# ardunio-physics-board-v4.net
KiCad netlist of a schematic drawn in EAGLE
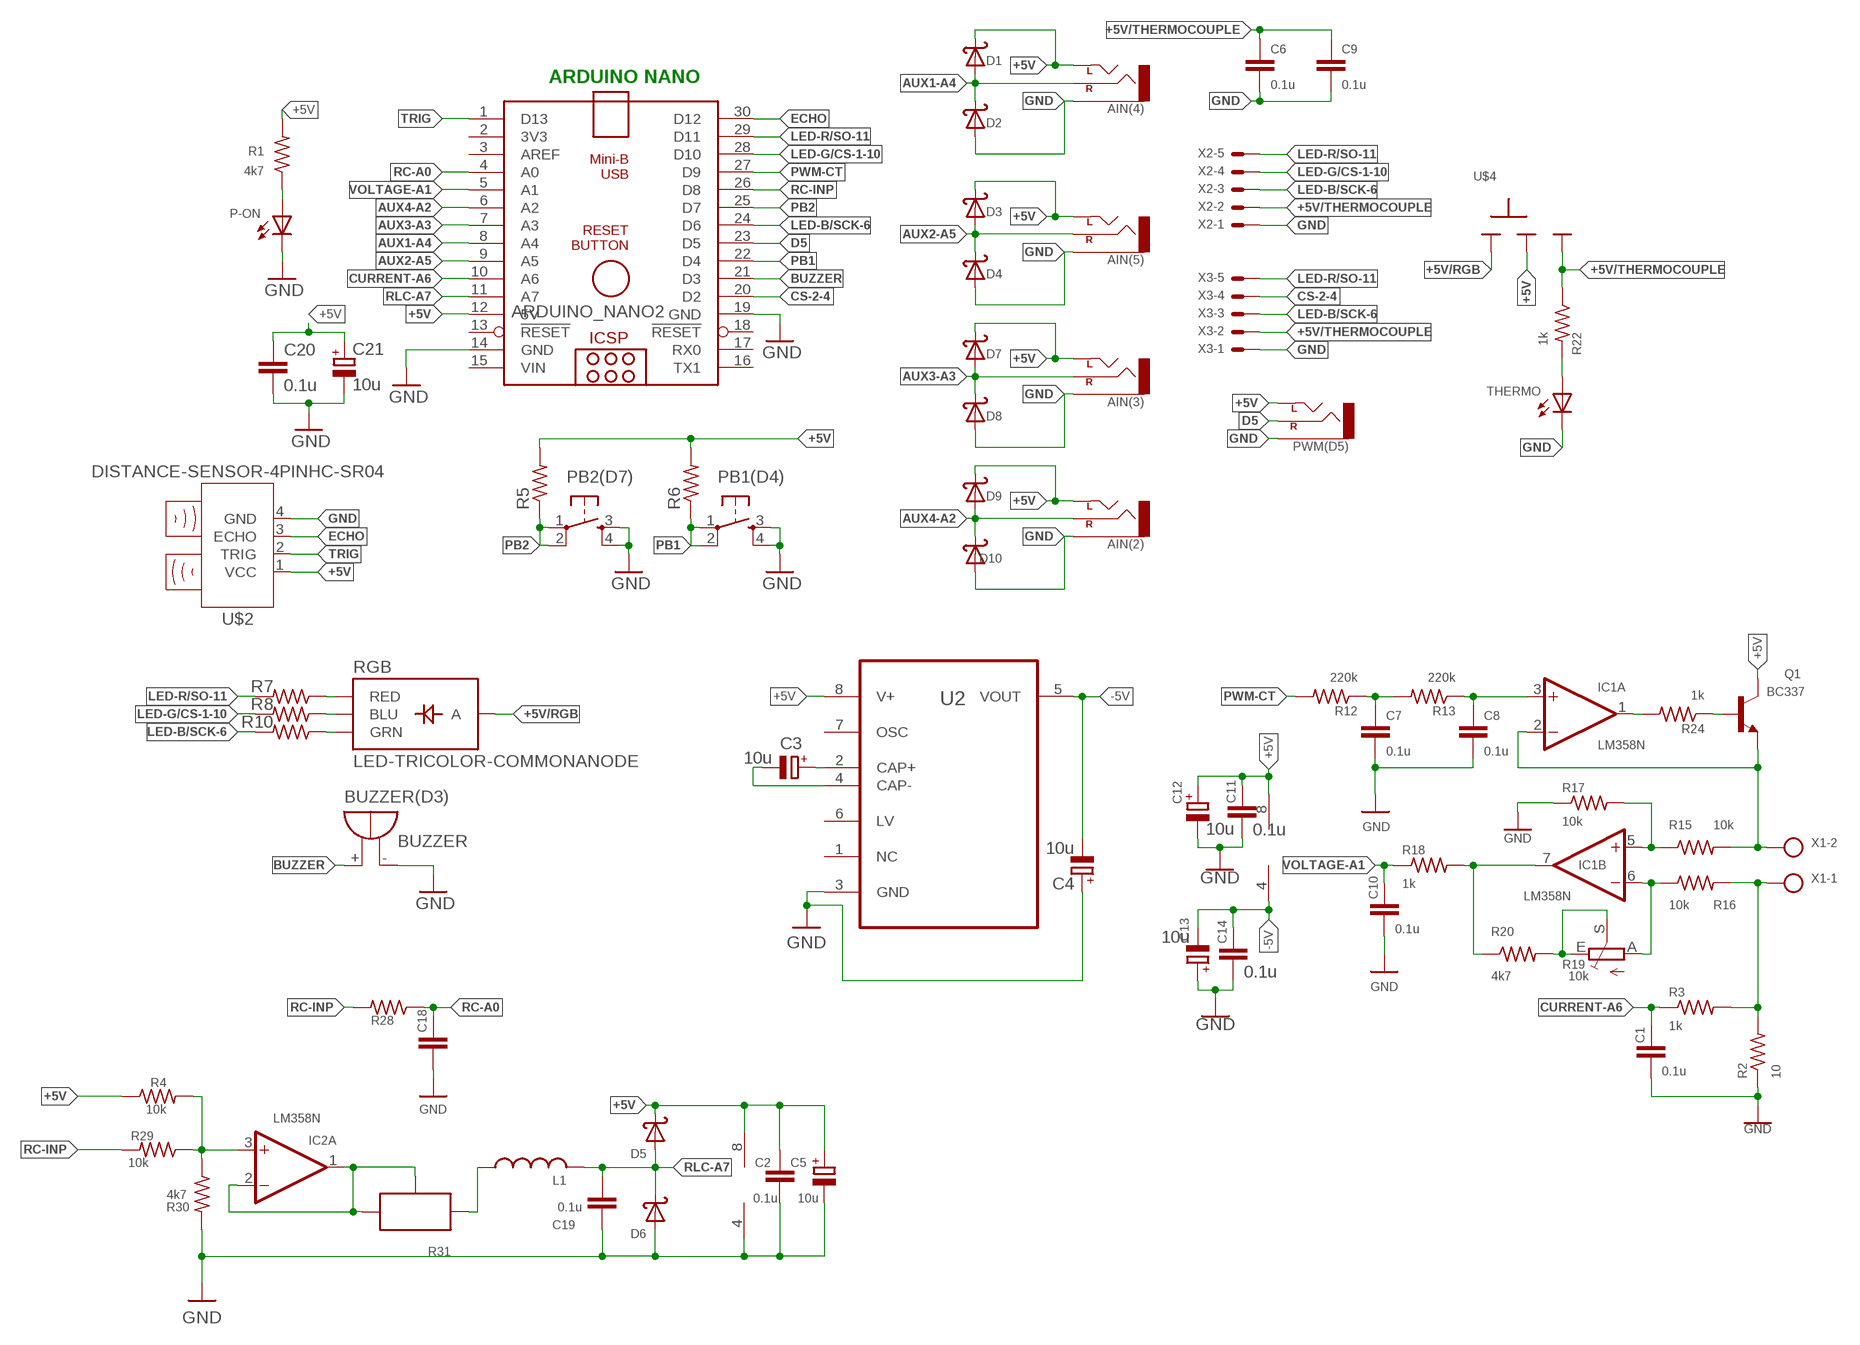
[diagram p0: schematic, sheet 1]

(export (version "E")
  (design (tool "Eeschema 10.0.6"))
  (components
    (comp (ref "AIN(2)")
      (value "AUX-CONNECTOR_CEDT_JANUARY_2015_V5_AUDIO-JACKPTH")
      (footprint "eagle-import:AUX-CONNECTOR_CEDT_JANUARY_2015_V5_AUDIO-JACK")
      (libsource (lib "eagle-import") (part "AUX-CONNECTOR_CEDT_JANUARY_2015_V5_AUDIO-JACKPTH"))
    )
    (comp (ref "AIN(3)")
      (value "AUX-CONNECTOR_CEDT_JANUARY_2015_V5_AUDIO-JACKPTH")
      (footprint "eagle-import:AUX-CONNECTOR_CEDT_JANUARY_2015_V5_AUDIO-JACK")
      (libsource (lib "eagle-import") (part "AUX-CONNECTOR_CEDT_JANUARY_2015_V5_AUDIO-JACKPTH"))
    )
    (comp (ref "AIN(4)")
      (value "AUX-CONNECTOR_CEDT_JANUARY_2015_V5_AUDIO-JACKPTH")
      (footprint "eagle-import:AUX-CONNECTOR_CEDT_JANUARY_2015_V5_AUDIO-JACK")
      (libsource (lib "eagle-import") (part "AUX-CONNECTOR_CEDT_JANUARY_2015_V5_AUDIO-JACKPTH"))
    )
    (comp (ref "AIN(5)")
      (value "AUX-CONNECTOR_CEDT_JANUARY_2015_V5_AUDIO-JACKPTH")
      (footprint "eagle-import:AUX-CONNECTOR_CEDT_JANUARY_2015_V5_AUDIO-JACK")
      (libsource (lib "eagle-import") (part "AUX-CONNECTOR_CEDT_JANUARY_2015_V5_AUDIO-JACKPTH"))
    )
    (comp (ref "ARDUINO_NANO2")
      (value "ARDUINONANOV30_ARDUINO_NANO")
      (footprint "eagle-import:ARDUINONANOV30_ARDUINO_NANO")
      (libsource (lib "eagle-import") (part "ARDUINONANOV30_ARDUINO_NANO"))
    )
    (comp (ref "BUZZER(D3)")
      (value "BUZZER")
      (footprint "eagle-import:F_TMB")
      (libsource (lib "eagle-import") (part "BUZZER"))
    )
    (comp (ref "C1")
      (value "0.1u")
      (footprint "eagle-import:C025-025X050")
      (libsource (lib "eagle-import") (part "C-EU025-025X050"))
    )
    (comp (ref "C2")
      (value "0.1u")
      (footprint "eagle-import:C025-025X050")
      (libsource (lib "eagle-import") (part "C-EU025-025X050"))
    )
    (comp (ref "C3")
      (value "10u")
      (footprint "eagle-import:TT2D5")
      (libsource (lib "eagle-import") (part "CPOL-EUTT2D5"))
    )
    (comp (ref "C4")
      (value "10u")
      (footprint "eagle-import:TT2D5")
      (libsource (lib "eagle-import") (part "CPOL-EUTT2D5"))
    )
    (comp (ref "C5")
      (value "10u")
      (footprint "eagle-import:TT2D5")
      (libsource (lib "eagle-import") (part "CPOL-EUTT2D5"))
    )
    (comp (ref "C6")
      (value "0.1u")
      (footprint "eagle-import:C025-024X044")
      (libsource (lib "eagle-import") (part "C-EU025-024X044"))
    )
    (comp (ref "C7")
      (value "0.1u")
      (footprint "eagle-import:C025-025X050")
      (libsource (lib "eagle-import") (part "C-EU025-025X050"))
    )
    (comp (ref "C8")
      (value "0.1u")
      (footprint "eagle-import:C025-025X050")
      (libsource (lib "eagle-import") (part "C-EU025-025X050"))
    )
    (comp (ref "C9")
      (value "0.1u")
      (footprint "eagle-import:C025-024X044")
      (libsource (lib "eagle-import") (part "C-EU025-024X044"))
    )
    (comp (ref "C10")
      (value "0.1u")
      (footprint "eagle-import:C025-025X050")
      (libsource (lib "eagle-import") (part "C-EU025-025X050"))
    )
    (comp (ref "C11")
      (value "0.1u")
      (footprint "eagle-import:C025-025X050")
      (libsource (lib "eagle-import") (part "C-EU025-025X050"))
    )
    (comp (ref "C12")
      (value "10u")
      (footprint "eagle-import:TT2D5")
      (libsource (lib "eagle-import") (part "CPOL-EUTT2D5"))
    )
    (comp (ref "C13")
      (value "10u")
      (footprint "eagle-import:TT2D5")
      (libsource (lib "eagle-import") (part "CPOL-EUTT2D5"))
    )
    (comp (ref "C14")
      (value "0.1u")
      (footprint "eagle-import:C025-025X050")
      (libsource (lib "eagle-import") (part "C-EU025-025X050"))
    )
    (comp (ref "C18")
      (value "C-EU025-025X050")
      (footprint "eagle-import:C025-025X050")
      (libsource (lib "eagle-import") (part "C-EU025-025X050"))
    )
    (comp (ref "C19")
      (value "0.1u")
      (footprint "eagle-import:C025-025X050")
      (libsource (lib "eagle-import") (part "C-EU025-025X050"))
    )
    (comp (ref "C20")
      (value "0.1u")
      (footprint "eagle-import:C025-024X044")
      (libsource (lib "eagle-import") (part "C-EU025-024X044"))
    )
    (comp (ref "C21")
      (value "10u")
      (footprint "eagle-import:E2,5-5")
      (libsource (lib "eagle-import") (part "CPOL-EUE2.5-5"))
    )
    (comp (ref "D1")
      (value "1N5819")
      (footprint "eagle-import:DO41-10")
      (libsource (lib "eagle-import") (part "1N5819"))
    )
    (comp (ref "D2")
      (value "1N5819")
      (footprint "eagle-import:DO41-10")
      (libsource (lib "eagle-import") (part "1N5819"))
    )
    (comp (ref "D3")
      (value "1N5819")
      (footprint "eagle-import:DO41-10")
      (libsource (lib "eagle-import") (part "1N5819"))
    )
    (comp (ref "D4")
      (value "1N5819")
      (footprint "eagle-import:DO41-10")
      (libsource (lib "eagle-import") (part "1N5819"))
    )
    (comp (ref "D5")
      (value "1N5819")
      (footprint "eagle-import:DO41-10")
      (libsource (lib "eagle-import") (part "1N5819"))
    )
    (comp (ref "D6")
      (value "1N5819")
      (footprint "eagle-import:DO41-10")
      (libsource (lib "eagle-import") (part "1N5819"))
    )
    (comp (ref "D7")
      (value "1N5819")
      (footprint "eagle-import:DO41-10")
      (libsource (lib "eagle-import") (part "1N5819"))
    )
    (comp (ref "D8")
      (value "1N5819")
      (footprint "eagle-import:DO41-10")
      (libsource (lib "eagle-import") (part "1N5819"))
    )
    (comp (ref "D9")
      (value "1N5819")
      (footprint "eagle-import:DO41-10")
      (libsource (lib "eagle-import") (part "1N5819"))
    )
    (comp (ref "D10")
      (value "1N5819")
      (footprint "eagle-import:DO41-10")
      (libsource (lib "eagle-import") (part "1N5819"))
    )
    (comp (ref "IC1")
      (value "LM358N")
      (footprint "eagle-import:DIL08")
      (libsource (lib "eagle-import") (part "LM358N"))
    )
    (comp (ref "IC2")
      (value "LM358N")
      (footprint "eagle-import:DIL08")
      (libsource (lib "eagle-import") (part "LM358N"))
    )
    (comp (ref "L1")
      (value "L-US6000-XXX-RC")
      (footprint "eagle-import:6000-XXXX-RC")
      (libsource (lib "eagle-import") (part "L-US6000-XXX-RC"))
    )
    (comp (ref "P-ON")
      (value "LED3MM")
      (footprint "eagle-import:LED3MM")
      (libsource (lib "eagle-import") (part "LED3MM"))
    )
    (comp (ref "PB1(D4)")
      (value "OMRON_SWITCH_40-XX")
      (footprint "eagle-import:B3F-40XX")
      (libsource (lib "eagle-import") (part "OMRON_SWITCH_40-XX"))
    )
    (comp (ref "PB2(D7)")
      (value "OMRON_SWITCH_40-XX")
      (footprint "eagle-import:B3F-40XX")
      (libsource (lib "eagle-import") (part "OMRON_SWITCH_40-XX"))
    )
    (comp (ref "PWM(D5)")
      (value "AUX-CONNECTOR_CEDT_JANUARY_2015_V5_AUDIO-JACKPTH")
      (footprint "eagle-import:AUX-CONNECTOR_CEDT_JANUARY_2015_V5_AUDIO-JACK")
      (libsource (lib "eagle-import") (part "AUX-CONNECTOR_CEDT_JANUARY_2015_V5_AUDIO-JACKPTH"))
    )
    (comp (ref "Q1")
      (value "BC337")
      (footprint "eagle-import:TO92")
      (libsource (lib "eagle-import") (part "BC337"))
    )
    (comp (ref "R1")
      (value "4k7")
      (footprint "eagle-import:0204_7")
      (libsource (lib "eagle-import") (part "R-US_0204/7"))
    )
    (comp (ref "R2")
      (value "10")
      (footprint "eagle-import:0207_10")
      (libsource (lib "eagle-import") (part "RESISTOR0207/10"))
    )
    (comp (ref "R3")
      (value "1k")
      (footprint "eagle-import:0204_7")
      (libsource (lib "eagle-import") (part "R-US_0204/7"))
    )
    (comp (ref "R4")
      (value "10k")
      (footprint "eagle-import:0207_10")
      (libsource (lib "eagle-import") (part "R-US_0207/10"))
    )
    (comp (ref "R5")
      (value "R-US_0204/7")
      (footprint "eagle-import:0204_7")
      (libsource (lib "eagle-import") (part "R-US_0204/7"))
    )
    (comp (ref "R6")
      (value "R-US_0204/7")
      (footprint "eagle-import:0204_7")
      (libsource (lib "eagle-import") (part "R-US_0204/7"))
    )
    (comp (ref "R7")
      (value "R-US_0207/10")
      (footprint "eagle-import:0207_10")
      (libsource (lib "eagle-import") (part "R-US_0207/10"))
    )
    (comp (ref "R8")
      (value "R-US_0207/10")
      (footprint "eagle-import:0207_10")
      (libsource (lib "eagle-import") (part "R-US_0207/10"))
    )
    (comp (ref "R10")
      (value "R-US_0207/10")
      (footprint "eagle-import:0207_10")
      (libsource (lib "eagle-import") (part "R-US_0207/10"))
    )
    (comp (ref "R12")
      (value "220k")
      (footprint "eagle-import:0207_10")
      (libsource (lib "eagle-import") (part "R-US_0207/10"))
    )
    (comp (ref "R13")
      (value "220k")
      (footprint "eagle-import:0204_7")
      (libsource (lib "eagle-import") (part "R-US_0204/7"))
    )
    (comp (ref "R15")
      (value "10k")
      (footprint "eagle-import:0204_7")
      (libsource (lib "eagle-import") (part "R-US_0204/7"))
    )
    (comp (ref "R16")
      (value "10k")
      (footprint "eagle-import:0204_7")
      (libsource (lib "eagle-import") (part "R-US_0204/7"))
    )
    (comp (ref "R17")
      (value "10k")
      (footprint "eagle-import:0204_7")
      (libsource (lib "eagle-import") (part "R-US_0204/7"))
    )
    (comp (ref "R18")
      (value "1k")
      (footprint "eagle-import:0204_7")
      (libsource (lib "eagle-import") (part "R-US_0204/7"))
    )
    (comp (ref "R19")
      (value "10k")
      (footprint "eagle-import:RJ9W")
      (libsource (lib "eagle-import") (part "TRIM_EU-RJ9W"))
    )
    (comp (ref "R20")
      (value "4k7")
      (footprint "eagle-import:0204_7")
      (libsource (lib "eagle-import") (part "R-US_0204/7"))
    )
    (comp (ref "R22")
      (value "1k")
      (footprint "eagle-import:0204_7")
      (libsource (lib "eagle-import") (part "R-US_0204/7"))
    )
    (comp (ref "R24")
      (value "1k")
      (footprint "eagle-import:0204_7")
      (libsource (lib "eagle-import") (part "R-US_0204/7"))
    )
    (comp (ref "R28")
      (value "R-US_0207/10")
      (footprint "eagle-import:0207_10")
      (libsource (lib "eagle-import") (part "R-US_0207/10"))
    )
    (comp (ref "R29")
      (value "10k")
      (footprint "eagle-import:0204_7")
      (libsource (lib "eagle-import") (part "R-US_0204/7"))
    )
    (comp (ref "R30")
      (value "4k7")
      (footprint "eagle-import:0207_10")
      (libsource (lib "eagle-import") (part "R-US_0207/10"))
    )
    (comp (ref "R31")
      (value "POTNORMAL")
      (footprint "eagle-import:RJ9W")
      (libsource (lib "eagle-import") (part "POTNORMAL"))
    )
    (comp (ref "RGB")
      (value "LED-TRICOLOR-COMMONANODE")
      (footprint "eagle-import:LED-TRICOLOR-THROUGHHOLE")
      (libsource (lib "eagle-import") (part "LED-TRICOLOR-COMMONANODE"))
    )
    (comp (ref "THERMO")
      (value "LED3MM")
      (footprint "eagle-import:LED3MM")
      (libsource (lib "eagle-import") (part "LED3MM"))
    )
    (comp (ref "U$2")
      (value "DISTANCE-SENSOR-4PINHC-SR04")
      (footprint "eagle-import:HC-SR04")
      (libsource (lib "eagle-import") (part "DISTANCE-SENSOR-4PINHC-SR04"))
    )
    (comp (ref "U$4")
      (value "SLIDESWITCH-BIG")
      (footprint "eagle-import:BIGSWITCH")
      (libsource (lib "eagle-import") (part "SLIDESWITCH-BIG"))
    )
    (comp (ref "U2")
      (value "ICL7660CPAZ_ICL7660CPAZ")
      (footprint "eagle-import:ICL7660CPAZ_DIP254P762X533-8")
      (fields (field (name "MF") "Renesas Electronics") (field (name "MP") "ICL7660CPAZ"))
      (libsource (lib "eagle-import") (part "ICL7660CPAZ_ICL7660CPAZ"))
    )
    (comp (ref "X1")
      (value "AK500/2-H")
      (footprint "eagle-import:AK500_2-H")
      (libsource (lib "eagle-import") (part "AK500/2-H"))
    )
    (comp (ref "X2")
      (value "JST-XH-05-PIN-LONG-PAD")
      (footprint "eagle-import:JST-XH-05-PACKAGE-LONG-PAD")
      (libsource (lib "eagle-import") (part "JST-XH-05-PIN-LONG-PAD"))
    )
    (comp (ref "X3")
      (value "JST-XH-05-PIN-LONG-PAD")
      (footprint "eagle-import:JST-XH-05-PACKAGE-LONG-PAD")
      (libsource (lib "eagle-import") (part "JST-XH-05-PIN-LONG-PAD"))
    )
  )
  (nets
    (net (code "1") (name "+5V") (class "Default")
      (node (ref "AIN(2)") (pin "TIP") (pinfunction "LEFT_TIP") (pintype "bidirectional"))
      (node (ref "AIN(3)") (pin "TIP") (pinfunction "LEFT_TIP") (pintype "bidirectional"))
      (node (ref "AIN(4)") (pin "TIP") (pinfunction "LEFT_TIP") (pintype "bidirectional"))
      (node (ref "AIN(5)") (pin "TIP") (pinfunction "LEFT_TIP") (pintype "bidirectional"))
      (node (ref "ARDUINO_NANO2") (pin "12") (pinfunction "5V_12") (pintype "power_in"))
      (node (ref "C11") (pin "1") (pinfunction "1_1") (pintype "passive"))
      (node (ref "C12") (pin "+") (pinfunction "+_+") (pintype "passive"))
      (node (ref "C2") (pin "1") (pinfunction "1_1") (pintype "passive"))
      (node (ref "C20") (pin "1") (pinfunction "1_1") (pintype "passive"))
      (node (ref "C21") (pin "+") (pinfunction "+_+") (pintype "passive"))
      (node (ref "C5") (pin "+") (pinfunction "+_+") (pintype "passive"))
      (node (ref "D1") (pin "C") (pinfunction "C_C") (pintype "passive"))
      (node (ref "D3") (pin "C") (pinfunction "C_C") (pintype "passive"))
      (node (ref "D5") (pin "C") (pinfunction "C_C") (pintype "passive"))
      (node (ref "D7") (pin "C") (pinfunction "C_C") (pintype "passive"))
      (node (ref "D9") (pin "C") (pinfunction "C_C") (pintype "passive"))
      (node (ref "IC1") (pin "8") (pinfunction "V+_8") (pintype "power_in"))
      (node (ref "IC2") (pin "8") (pinfunction "V+_8") (pintype "power_in"))
      (node (ref "PWM(D5)") (pin "TIP") (pinfunction "LEFT_TIP") (pintype "bidirectional"))
      (node (ref "Q1") (pin "3") (pinfunction "C_3") (pintype "passive"))
      (node (ref "R1") (pin "2") (pinfunction "2_2") (pintype "passive"))
      (node (ref "R4") (pin "1") (pinfunction "1_1") (pintype "passive"))
      (node (ref "R5") (pin "2") (pinfunction "2_2") (pintype "passive"))
      (node (ref "R6") (pin "2") (pinfunction "2_2") (pintype "passive"))
      (node (ref "U$2") (pin "1") (pinfunction "VCC_1") (pintype "bidirectional"))
      (node (ref "U$4") (pin "2") (pinfunction "2_2") (pintype "bidirectional"))
      (node (ref "U2") (pin "8") (pinfunction "V+_8") (pintype "power_in"))
    )
    (net (code "2") (name "+5V{slash}RGB") (class "Default")
      (node (ref "RGB") (pin "ANODE") (pinfunction "A_ANODE") (pintype "bidirectional"))
      (node (ref "U$4") (pin "1") (pinfunction "1_1") (pintype "bidirectional"))
    )
    (net (code "3") (name "+5V{slash}THERMOCOUPLE") (class "Default")
      (node (ref "C6") (pin "1") (pinfunction "1_1") (pintype "passive"))
      (node (ref "C9") (pin "1") (pinfunction "1_1") (pintype "passive"))
      (node (ref "R22") (pin "1") (pinfunction "1_1") (pintype "passive"))
      (node (ref "U$4") (pin "3") (pinfunction "3_3") (pintype "bidirectional"))
      (node (ref "X2") (pin "2") (pinfunction "S_2") (pintype "passive"))
      (node (ref "X3") (pin "2") (pinfunction "S_2") (pintype "passive"))
    )
    (net (code "4") (name "-5V") (class "Default")
      (node (ref "C13") (pin "-") (pinfunction "-_-") (pintype "passive"))
      (node (ref "C14") (pin "1") (pinfunction "1_1") (pintype "passive"))
      (node (ref "C4") (pin "-") (pinfunction "-_-") (pintype "passive"))
      (node (ref "IC1") (pin "4") (pinfunction "V-_4") (pintype "power_in"))
      (node (ref "U2") (pin "5") (pinfunction "VOUT_5") (pintype "output"))
    )
    (net (code "5") (name "/VIN") (class "Default")
      (node (ref "ARDUINO_NANO2") (pin "15") (pinfunction "VIN_15") (pintype "power_in"))
    )
    (net (code "6") (name "AUX1-A4") (class "Default")
      (node (ref "AIN(4)") (pin "RING") (pinfunction "RIGHT_RING") (pintype "bidirectional"))
      (node (ref "ARDUINO_NANO2") (pin "8") (pinfunction "A4_8") (pintype "bidirectional"))
      (node (ref "D1") (pin "A") (pinfunction "A_A") (pintype "passive"))
      (node (ref "D2") (pin "C") (pinfunction "C_C") (pintype "passive"))
    )
    (net (code "7") (name "AUX2-A5") (class "Default")
      (node (ref "AIN(5)") (pin "RING") (pinfunction "RIGHT_RING") (pintype "bidirectional"))
      (node (ref "ARDUINO_NANO2") (pin "9") (pinfunction "A5_9") (pintype "bidirectional"))
      (node (ref "D3") (pin "A") (pinfunction "A_A") (pintype "passive"))
      (node (ref "D4") (pin "C") (pinfunction "C_C") (pintype "passive"))
    )
    (net (code "8") (name "AUX3-A3") (class "Default")
      (node (ref "AIN(3)") (pin "RING") (pinfunction "RIGHT_RING") (pintype "bidirectional"))
      (node (ref "ARDUINO_NANO2") (pin "7") (pinfunction "A3_7") (pintype "bidirectional"))
      (node (ref "D7") (pin "A") (pinfunction "A_A") (pintype "passive"))
      (node (ref "D8") (pin "C") (pinfunction "C_C") (pintype "passive"))
    )
    (net (code "9") (name "AUX4-A2") (class "Default")
      (node (ref "AIN(2)") (pin "RING") (pinfunction "RIGHT_RING") (pintype "bidirectional"))
      (node (ref "ARDUINO_NANO2") (pin "6") (pinfunction "A2_6") (pintype "bidirectional"))
      (node (ref "D10") (pin "C") (pinfunction "C_C") (pintype "passive"))
      (node (ref "D9") (pin "A") (pinfunction "A_A") (pintype "passive"))
    )
    (net (code "10") (name "BUZZER") (class "Default")
      (node (ref "ARDUINO_NANO2") (pin "21") (pinfunction "D3_21") (pintype "bidirectional"))
      (node (ref "BUZZER(D3)") (pin "+") (pinfunction "+_+") (pintype "passive"))
    )
    (net (code "11") (name "CS-2-4") (class "Default")
      (node (ref "ARDUINO_NANO2") (pin "20") (pinfunction "D2_20") (pintype "bidirectional"))
      (node (ref "X3") (pin "4") (pinfunction "S_4") (pintype "passive"))
    )
    (net (code "12") (name "CURRENT-A6") (class "Default")
      (node (ref "ARDUINO_NANO2") (pin "10") (pinfunction "A6_10") (pintype "bidirectional"))
      (node (ref "C1") (pin "1") (pinfunction "1_1") (pintype "passive"))
      (node (ref "R3") (pin "1") (pinfunction "1_1") (pintype "passive"))
    )
    (net (code "13") (name "D5") (class "Default")
      (node (ref "ARDUINO_NANO2") (pin "23") (pinfunction "D5_23") (pintype "bidirectional"))
      (node (ref "PWM(D5)") (pin "RING") (pinfunction "RIGHT_RING") (pintype "bidirectional"))
    )
    (net (code "14") (name "ECHO") (class "Default")
      (node (ref "ARDUINO_NANO2") (pin "30") (pinfunction "D12_30") (pintype "bidirectional"))
      (node (ref "U$2") (pin "3") (pinfunction "ECHO_3") (pintype "bidirectional"))
    )
    (net (code "15") (name "GND") (class "Default")
      (node (ref "AIN(2)") (pin "SLEEVE") (pinfunction "SLEEVE_SLEEVE") (pintype "bidirectional"))
      (node (ref "AIN(3)") (pin "SLEEVE") (pinfunction "SLEEVE_SLEEVE") (pintype "bidirectional"))
      (node (ref "AIN(4)") (pin "SLEEVE") (pinfunction "SLEEVE_SLEEVE") (pintype "bidirectional"))
      (node (ref "AIN(5)") (pin "SLEEVE") (pinfunction "SLEEVE_SLEEVE") (pintype "bidirectional"))
      (node (ref "ARDUINO_NANO2") (pin "14") (pinfunction "GND_14") (pintype "power_in"))
      (node (ref "ARDUINO_NANO2") (pin "19") (pinfunction "GND_19") (pintype "power_in"))
      (node (ref "BUZZER(D3)") (pin "-") (pinfunction "-_-") (pintype "passive"))
      (node (ref "C1") (pin "2") (pinfunction "2_2") (pintype "passive"))
      (node (ref "C10") (pin "2") (pinfunction "2_2") (pintype "passive"))
      (node (ref "C11") (pin "2") (pinfunction "2_2") (pintype "passive"))
      (node (ref "C12") (pin "-") (pinfunction "-_-") (pintype "passive"))
      (node (ref "C13") (pin "+") (pinfunction "+_+") (pintype "passive"))
      (node (ref "C14") (pin "2") (pinfunction "2_2") (pintype "passive"))
      (node (ref "C18") (pin "2") (pinfunction "2_2") (pintype "passive"))
      (node (ref "C19") (pin "2") (pinfunction "2_2") (pintype "passive"))
      (node (ref "C2") (pin "2") (pinfunction "2_2") (pintype "passive"))
      (node (ref "C20") (pin "2") (pinfunction "2_2") (pintype "passive"))
      (node (ref "C21") (pin "-") (pinfunction "-_-") (pintype "passive"))
      (node (ref "C4") (pin "+") (pinfunction "+_+") (pintype "passive"))
      (node (ref "C5") (pin "-") (pinfunction "-_-") (pintype "passive"))
      (node (ref "C6") (pin "2") (pinfunction "2_2") (pintype "passive"))
      (node (ref "C7") (pin "2") (pinfunction "2_2") (pintype "passive"))
      (node (ref "C8") (pin "2") (pinfunction "2_2") (pintype "passive"))
      (node (ref "C9") (pin "2") (pinfunction "2_2") (pintype "passive"))
      (node (ref "D10") (pin "A") (pinfunction "A_A") (pintype "passive"))
      (node (ref "D2") (pin "A") (pinfunction "A_A") (pintype "passive"))
      (node (ref "D4") (pin "A") (pinfunction "A_A") (pintype "passive"))
      (node (ref "D6") (pin "A") (pinfunction "A_A") (pintype "passive"))
      (node (ref "D8") (pin "A") (pinfunction "A_A") (pintype "passive"))
      (node (ref "IC2") (pin "4") (pinfunction "V-_4") (pintype "power_in"))
      (node (ref "P-ON") (pin "K") (pinfunction "C_K") (pintype "passive"))
      (node (ref "PB1(D4)") (pin "3") (pinfunction "S_3") (pintype "passive"))
      (node (ref "PB1(D4)") (pin "4") (pinfunction "S1_4") (pintype "passive"))
      (node (ref "PB2(D7)") (pin "3") (pinfunction "S_3") (pintype "passive"))
      (node (ref "PB2(D7)") (pin "4") (pinfunction "S1_4") (pintype "passive"))
      (node (ref "PWM(D5)") (pin "SLEEVE") (pinfunction "SLEEVE_SLEEVE") (pintype "bidirectional"))
      (node (ref "R17") (pin "1") (pinfunction "1_1") (pintype "passive"))
      (node (ref "R2") (pin "1") (pinfunction "1_1") (pintype "passive"))
      (node (ref "R30") (pin "2") (pinfunction "2_2") (pintype "passive"))
      (node (ref "THERMO") (pin "K") (pinfunction "C_K") (pintype "passive"))
      (node (ref "U$2") (pin "4") (pinfunction "GND_4") (pintype "bidirectional"))
      (node (ref "U2") (pin "3") (pinfunction "GND_3") (pintype "passive"))
      (node (ref "X2") (pin "1") (pinfunction "S_1") (pintype "passive"))
      (node (ref "X3") (pin "1") (pinfunction "S_1") (pintype "passive"))
    )
    (net (code "16") (name "LED-B{slash}SCK-6") (class "Default")
      (node (ref "ARDUINO_NANO2") (pin "24") (pinfunction "D6_24") (pintype "bidirectional"))
      (node (ref "R10") (pin "2") (pinfunction "2_2") (pintype "passive"))
      (node (ref "X2") (pin "3") (pinfunction "S_3") (pintype "passive"))
      (node (ref "X3") (pin "3") (pinfunction "S_3") (pintype "passive"))
    )
    (net (code "17") (name "LED-G{slash}CS-1-10") (class "Default")
      (node (ref "ARDUINO_NANO2") (pin "28") (pinfunction "D10_28") (pintype "bidirectional"))
      (node (ref "R8") (pin "2") (pinfunction "2_2") (pintype "passive"))
      (node (ref "X2") (pin "4") (pinfunction "S_4") (pintype "passive"))
    )
    (net (code "18") (name "LED-R{slash}SO-11") (class "Default")
      (node (ref "ARDUINO_NANO2") (pin "29") (pinfunction "D11_29") (pintype "bidirectional"))
      (node (ref "R7") (pin "2") (pinfunction "2_2") (pintype "passive"))
      (node (ref "X2") (pin "5") (pinfunction "S_5") (pintype "passive"))
      (node (ref "X3") (pin "5") (pinfunction "S_5") (pintype "passive"))
    )
    (net (code "19") (name "Net-(C7-Pad1)") (class "Default")
      (node (ref "C7") (pin "1") (pinfunction "1_1") (pintype "passive"))
      (node (ref "R12") (pin "1") (pinfunction "1_1") (pintype "passive"))
      (node (ref "R13") (pin "2") (pinfunction "2_2") (pintype "passive"))
    )
    (net (code "20") (name "Net-(IC1A-+IN)") (class "Default")
      (node (ref "C8") (pin "1") (pinfunction "1_1") (pintype "passive"))
      (node (ref "IC1") (pin "3") (pinfunction "+IN_3") (pintype "input"))
      (node (ref "R13") (pin "1") (pinfunction "1_1") (pintype "passive"))
    )
    (net (code "21") (name "Net-(IC1A--IN)") (class "Default")
      (node (ref "IC1") (pin "2") (pinfunction "-IN_2") (pintype "input"))
      (node (ref "Q1") (pin "1") (pinfunction "E_1") (pintype "passive"))
      (node (ref "R15") (pin "2") (pinfunction "2_2") (pintype "passive"))
      (node (ref "X1") (pin "2") (pinfunction "KL_2") (pintype "passive"))
    )
    (net (code "22") (name "Net-(IC1A-OUT)") (class "Default")
      (node (ref "IC1") (pin "1") (pinfunction "OUT_1") (pintype "output"))
      (node (ref "R24") (pin "2") (pinfunction "2_2") (pintype "passive"))
    )
    (net (code "23") (name "Net-(IC1B-+IN)") (class "Default")
      (node (ref "IC1") (pin "5") (pinfunction "+IN_5") (pintype "input"))
      (node (ref "R15") (pin "1") (pinfunction "1_1") (pintype "passive"))
      (node (ref "R17") (pin "2") (pinfunction "2_2") (pintype "passive"))
    )
    (net (code "24") (name "Net-(IC1B--IN)") (class "Default")
      (node (ref "IC1") (pin "6") (pinfunction "-IN_6") (pintype "input"))
      (node (ref "R16") (pin "1") (pinfunction "1_1") (pintype "passive"))
      (node (ref "R19") (pin "A") (pinfunction "A_A") (pintype "passive"))
    )
    (net (code "25") (name "Net-(IC1B-OUT)") (class "Default")
      (node (ref "IC1") (pin "7") (pinfunction "OUT_7") (pintype "output"))
      (node (ref "R18") (pin "2") (pinfunction "2_2") (pintype "passive"))
      (node (ref "R20") (pin "1") (pinfunction "1_1") (pintype "passive"))
    )
    (net (code "26") (name "Net-(IC2A-+IN)") (class "Default")
      (node (ref "IC2") (pin "3") (pinfunction "+IN_3") (pintype "input"))
      (node (ref "R29") (pin "1") (pinfunction "1_1") (pintype "passive"))
      (node (ref "R30") (pin "1") (pinfunction "1_1") (pintype "passive"))
      (node (ref "R4") (pin "2") (pinfunction "2_2") (pintype "passive"))
    )
    (net (code "27") (name "Net-(IC2A--IN)") (class "Default")
      (node (ref "IC2") (pin "1") (pinfunction "OUT_1") (pintype "output"))
      (node (ref "IC2") (pin "2") (pinfunction "-IN_2") (pintype "input"))
      (node (ref "R31") (pin "A") (pinfunction "A_A") (pintype "passive"))
      (node (ref "R31") (pin "S") (pinfunction "S_S") (pintype "passive"))
    )
    (net (code "28") (name "Net-(L1-Pad1)") (class "Default")
      (node (ref "L1") (pin "1") (pinfunction "1_1") (pintype "passive"))
      (node (ref "R31") (pin "E") (pinfunction "E_E") (pintype "passive"))
    )
    (net (code "29") (name "Net-(P-ON-PadA)") (class "Default")
      (node (ref "P-ON") (pin "A") (pinfunction "A_A") (pintype "passive"))
      (node (ref "R1") (pin "1") (pinfunction "1_1") (pintype "passive"))
    )
    (net (code "30") (name "Net-(Q1-B)") (class "Default")
      (node (ref "Q1") (pin "2") (pinfunction "B_2") (pintype "passive"))
      (node (ref "R24") (pin "1") (pinfunction "1_1") (pintype "passive"))
    )
    (net (code "31") (name "Net-(R7-Pad1)") (class "Default")
      (node (ref "R7") (pin "1") (pinfunction "1_1") (pintype "passive"))
      (node (ref "RGB") (pin "RED") (pinfunction "RED_RED") (pintype "bidirectional"))
    )
    (net (code "32") (name "Net-(R8-Pad1)") (class "Default")
      (node (ref "R8") (pin "1") (pinfunction "1_1") (pintype "passive"))
      (node (ref "RGB") (pin "BLU") (pinfunction "BLU_BLU") (pintype "bidirectional"))
    )
    (net (code "33") (name "Net-(R10-Pad1)") (class "Default")
      (node (ref "R10") (pin "1") (pinfunction "1_1") (pintype "passive"))
      (node (ref "RGB") (pin "GRN") (pinfunction "GRN_GRN") (pintype "bidirectional"))
    )
    (net (code "34") (name "Net-(R19-PadE)") (class "Default")
      (node (ref "R19") (pin "E") (pinfunction "E_E") (pintype "passive"))
      (node (ref "R19") (pin "S") (pinfunction "S_S") (pintype "passive"))
      (node (ref "R20") (pin "2") (pinfunction "2_2") (pintype "passive"))
    )
    (net (code "35") (name "Net-(R22-Pad2)") (class "Default")
      (node (ref "R22") (pin "2") (pinfunction "2_2") (pintype "passive"))
      (node (ref "THERMO") (pin "A") (pinfunction "A_A") (pintype "passive"))
    )
    (net (code "36") (name "Net-(U2-CAP+)") (class "Default")
      (node (ref "C3") (pin "+") (pinfunction "+_+") (pintype "passive"))
      (node (ref "U2") (pin "2") (pinfunction "CAP+_2") (pintype "input"))
    )
    (net (code "37") (name "Net-(U2-CAP-)") (class "Default")
      (node (ref "C3") (pin "-") (pinfunction "-_-") (pintype "passive"))
      (node (ref "U2") (pin "4") (pinfunction "CAP-_4") (pintype "input"))
    )
    (net (code "38") (name "Net-(X1A-KL)") (class "Default")
      (node (ref "R16") (pin "2") (pinfunction "2_2") (pintype "passive"))
      (node (ref "R2") (pin "2") (pinfunction "2_2") (pintype "passive"))
      (node (ref "R3") (pin "2") (pinfunction "2_2") (pintype "passive"))
      (node (ref "X1") (pin "1") (pinfunction "KL_1") (pintype "passive"))
    )
    (net (code "39") (name "PB1") (class "Default")
      (node (ref "ARDUINO_NANO2") (pin "22") (pinfunction "D4_22") (pintype "bidirectional"))
      (node (ref "PB1(D4)") (pin "1") (pinfunction "P_1") (pintype "passive"))
      (node (ref "PB1(D4)") (pin "2") (pinfunction "P1_2") (pintype "passive"))
      (node (ref "R6") (pin "1") (pinfunction "1_1") (pintype "passive"))
    )
    (net (code "40") (name "PB2") (class "Default")
      (node (ref "ARDUINO_NANO2") (pin "25") (pinfunction "D7_25") (pintype "bidirectional"))
      (node (ref "PB2(D7)") (pin "1") (pinfunction "P_1") (pintype "passive"))
      (node (ref "PB2(D7)") (pin "2") (pinfunction "P1_2") (pintype "passive"))
      (node (ref "R5") (pin "1") (pinfunction "1_1") (pintype "passive"))
    )
    (net (code "41") (name "PWM-CT") (class "Default")
      (node (ref "ARDUINO_NANO2") (pin "27") (pinfunction "D9_27") (pintype "bidirectional"))
      (node (ref "R12") (pin "2") (pinfunction "2_2") (pintype "passive"))
    )
    (net (code "42") (name "RC-A0") (class "Default")
      (node (ref "ARDUINO_NANO2") (pin "4") (pinfunction "A0_4") (pintype "bidirectional"))
      (node (ref "C18") (pin "1") (pinfunction "1_1") (pintype "passive"))
      (node (ref "R28") (pin "1") (pinfunction "1_1") (pintype "passive"))
    )
    (net (code "43") (name "RC-INP") (class "Default")
      (node (ref "ARDUINO_NANO2") (pin "26") (pinfunction "D8_26") (pintype "bidirectional"))
      (node (ref "R28") (pin "2") (pinfunction "2_2") (pintype "passive"))
      (node (ref "R29") (pin "2") (pinfunction "2_2") (pintype "passive"))
    )
    (net (code "44") (name "RLC-A7") (class "Default")
      (node (ref "ARDUINO_NANO2") (pin "11") (pinfunction "A7_11") (pintype "bidirectional"))
      (node (ref "C19") (pin "1") (pinfunction "1_1") (pintype "passive"))
      (node (ref "D5") (pin "A") (pinfunction "A_A") (pintype "passive"))
      (node (ref "D6") (pin "C") (pinfunction "C_C") (pintype "passive"))
      (node (ref "L1") (pin "2") (pinfunction "2_2") (pintype "passive"))
    )
    (net (code "45") (name "TRIG") (class "Default")
      (node (ref "ARDUINO_NANO2") (pin "1") (pinfunction "D13_1") (pintype "bidirectional"))
      (node (ref "U$2") (pin "2") (pinfunction "TRIG_2") (pintype "bidirectional"))
    )
    (net (code "46") (name "VOLTAGE-A1") (class "Default")
      (node (ref "ARDUINO_NANO2") (pin "5") (pinfunction "A1_5") (pintype "bidirectional"))
      (node (ref "C10") (pin "1") (pinfunction "1_1") (pintype "passive"))
      (node (ref "R18") (pin "1") (pinfunction "1_1") (pintype "passive"))
    )
    (net (code "47") (name "unconnected-(ARDUINO_NANO2-3V3-Pad2)") (class "Default")
      (node (ref "ARDUINO_NANO2") (pin "2") (pinfunction "3V3_2") (pintype "output"))
    )
    (net (code "48") (name "unconnected-(ARDUINO_NANO2-AREF-Pad3)") (class "Default")
      (node (ref "ARDUINO_NANO2") (pin "3") (pinfunction "AREF_3") (pintype "input"))
    )
    (net (code "49") (name "unconnected-(ARDUINO_NANO2-RX0-Pad17)") (class "Default")
      (node (ref "ARDUINO_NANO2") (pin "17") (pinfunction "RX0_17") (pintype "bidirectional"))
    )
    (net (code "50") (name "unconnected-(ARDUINO_NANO2-TX1-Pad16)") (class "Default")
      (node (ref "ARDUINO_NANO2") (pin "16") (pinfunction "TX1_16") (pintype "bidirectional"))
    )
    (net (code "51") (name "unconnected-(ARDUINO_NANO2-~{RESET}-Pad13)") (class "Default")
      (node (ref "ARDUINO_NANO2") (pin "13") (pinfunction "~{RESET}_13") (pintype "input"))
    )
    (net (code "52") (name "unconnected-(ARDUINO_NANO2-~{RESET}-Pad18)") (class "Default")
      (node (ref "ARDUINO_NANO2") (pin "18") (pinfunction "~{RESET}_18") (pintype "input"))
    )
    (net (code "53") (name "unconnected-(U2-LV-Pad6)") (class "Default")
      (node (ref "U2") (pin "6") (pinfunction "LV_6") (pintype "passive"))
    )
    (net (code "54") (name "unconnected-(U2-NC-Pad1)") (class "Default")
      (node (ref "U2") (pin "1") (pinfunction "NC_1") (pintype "no_connect"))
    )
    (net (code "55") (name "unconnected-(U2-OSC-Pad7)") (class "Default")
      (node (ref "U2") (pin "7") (pinfunction "OSC_7") (pintype "input"))
    )
  )
)
